# main.net
KiCad netlist of a schematic drawn in EAGLE
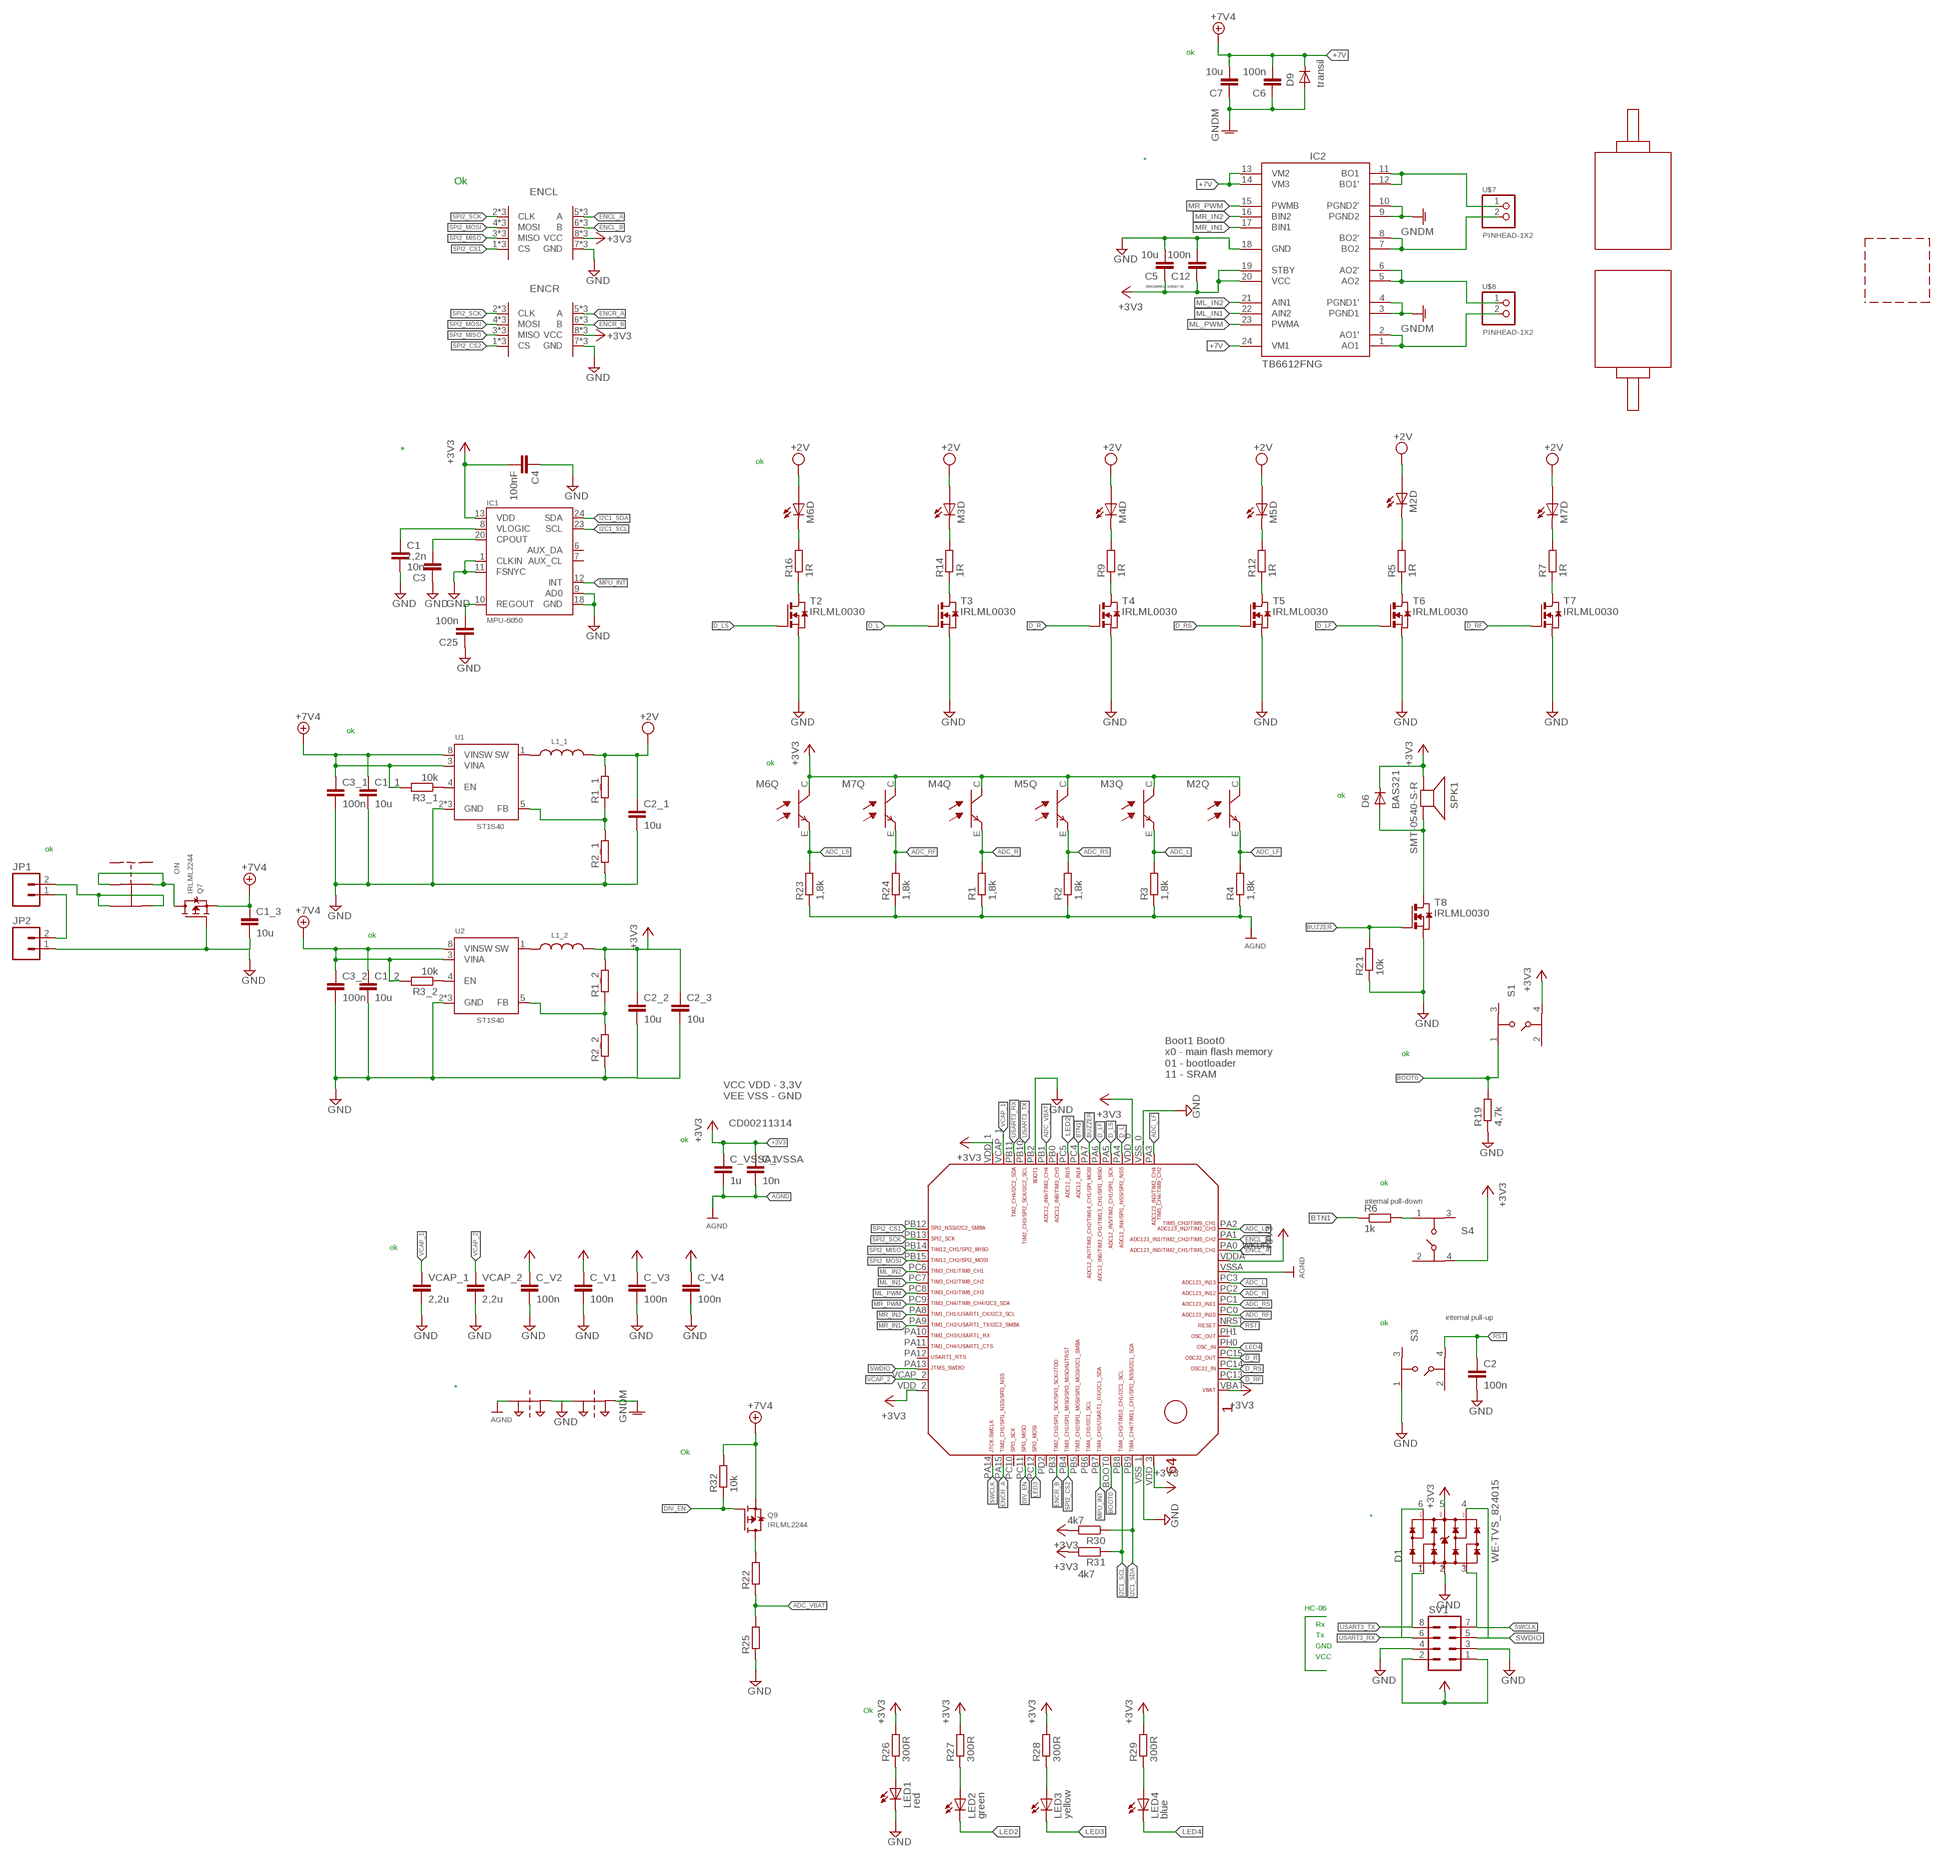
[diagram p0: schematic, sheet 1]

(export (version "E")
  (design (tool "Eeschema 10.0.6"))
  (components
    (comp (ref "C1")
      (value "10n")
      (footprint "eagle-import:C0603")
      (libsource (lib "eagle-import") (part "C-EUC0603"))
    )
    (comp (ref "C1_1")
      (value "10u")
      (footprint "eagle-import:C0805")
      (libsource (lib "eagle-import") (part "C-EUC0805"))
    )
    (comp (ref "C1_2")
      (value "10u")
      (footprint "eagle-import:C0805")
      (libsource (lib "eagle-import") (part "C-EUC0805"))
    )
    (comp (ref "C1_3")
      (value "10u")
      (footprint "eagle-import:C0805")
      (libsource (lib "eagle-import") (part "C-EUC0805"))
    )
    (comp (ref "C2")
      (value "100n")
      (footprint "eagle-import:C0603")
      (libsource (lib "eagle-import") (part "C-EUC0603"))
    )
    (comp (ref "C2_1")
      (value "10u")
      (footprint "eagle-import:C0805")
      (libsource (lib "eagle-import") (part "C-EUC0805"))
    )
    (comp (ref "C2_2")
      (value "10u")
      (footprint "eagle-import:C0805")
      (libsource (lib "eagle-import") (part "C-EUC0805"))
    )
    (comp (ref "C2_3")
      (value "10u")
      (footprint "eagle-import:C0805")
      (libsource (lib "eagle-import") (part "C-EUC0805"))
    )
    (comp (ref "C3")
      (value "2,2n")
      (footprint "eagle-import:C0603")
      (libsource (lib "eagle-import") (part "C-EUC0603"))
    )
    (comp (ref "C3_1")
      (value "100n")
      (footprint "eagle-import:C0603")
      (libsource (lib "eagle-import") (part "C-EUC0603"))
    )
    (comp (ref "C3_2")
      (value "100n")
      (footprint "eagle-import:C0603")
      (libsource (lib "eagle-import") (part "C-EUC0603"))
    )
    (comp (ref "C4")
      (value "100nF")
      (footprint "eagle-import:C0603")
      (libsource (lib "eagle-import") (part "C-EUC0603"))
    )
    (comp (ref "C5")
      (value "10u")
      (footprint "eagle-import:C0805")
      (libsource (lib "eagle-import") (part "C-EUC0805"))
    )
    (comp (ref "C6")
      (value "100n")
      (footprint "eagle-import:C0603")
      (libsource (lib "eagle-import") (part "C-EUC0603"))
    )
    (comp (ref "C7")
      (value "10u")
      (footprint "eagle-import:C1206")
      (libsource (lib "eagle-import") (part "C-EUC1206"))
    )
    (comp (ref "C12")
      (value "100n")
      (footprint "eagle-import:C0603")
      (libsource (lib "eagle-import") (part "C-EUC0603"))
    )
    (comp (ref "C25")
      (value "100n")
      (footprint "eagle-import:C0603")
      (libsource (lib "eagle-import") (part "C-EUC0603"))
    )
    (comp (ref "C_V1")
      (value "100n")
      (footprint "eagle-import:C0603")
      (libsource (lib "eagle-import") (part "C-EUC0603"))
    )
    (comp (ref "C_V2")
      (value "100n")
      (footprint "eagle-import:C0603")
      (libsource (lib "eagle-import") (part "C-EUC0603"))
    )
    (comp (ref "C_V3")
      (value "100n")
      (footprint "eagle-import:C0603")
      (libsource (lib "eagle-import") (part "C-EUC0603"))
    )
    (comp (ref "C_V4")
      (value "100n")
      (footprint "eagle-import:C0603")
      (libsource (lib "eagle-import") (part "C-EUC0603"))
    )
    (comp (ref "C_VSSA")
      (value "10n")
      (footprint "eagle-import:C0603")
      (libsource (lib "eagle-import") (part "C-EUC0603"))
    )
    (comp (ref "C_VSSA1")
      (value "1u")
      (footprint "eagle-import:C0603")
      (libsource (lib "eagle-import") (part "C-EUC0603"))
    )
    (comp (ref "D1")
      (value "WE-TVS_824015")
      (footprint "eagle-import:WE-TVS_SOT23-6L")
      (libsource (lib "eagle-import") (part "WE-TVS_824015"))
    )
    (comp (ref "D6")
      (value "BAS321")
      (footprint "eagle-import:SOD323(F)")
      (libsource (lib "eagle-import") (part "BAS321"))
    )
    (comp (ref "D9")
      (value "transil")
      (footprint "eagle-import:SOD323(F)")
      (libsource (lib "eagle-import") (part "BAS321"))
    )
    (comp (ref "IC1")
      (value "MPU-6050")
      (footprint "eagle-import:QFN.24.4X4")
      (libsource (lib "eagle-import") (part "MPU-6050"))
    )
    (comp (ref "IC2")
      (value "TB6612FNG")
      (footprint "eagle-import:SSOP24")
      (libsource (lib "eagle-import") (part "TB6612FNG"))
    )
    (comp (ref "JP1")
      (value "M02POLAR")
      (footprint "eagle-import:MOLEX-1X2")
      (libsource (lib "eagle-import") (part "M02POLAR"))
    )
    (comp (ref "JP2")
      (value "M02POLAR")
      (footprint "eagle-import:MOLEX-1X2")
      (libsource (lib "eagle-import") (part "M02POLAR"))
    )
    (comp (ref "L1")
      (value "LABITYNT")
      (footprint "eagle-import:LABIRYNT")
      (libsource (lib "eagle-import") (part "LABITYNT"))
    )
    (comp (ref "L1_1")
      (value "WE-MAIA_3015_78438335068")
      (footprint "eagle-import:WE-MAIA_3015")
      (libsource (lib "eagle-import") (part "WE-MAIA_3015_78438335068"))
    )
    (comp (ref "L1_2")
      (value "WE-MAIA_3015_78438335033")
      (footprint "eagle-import:WE-MAIA_3015")
      (libsource (lib "eagle-import") (part "WE-MAIA_3015_78438335033"))
    )
    (comp (ref "LED1")
      (value "red")
      (footprint "eagle-import:SML1206")
      (libsource (lib "eagle-import") (part "LEDSML1206"))
    )
    (comp (ref "LED2")
      (value "green")
      (footprint "eagle-import:SML1206")
      (libsource (lib "eagle-import") (part "LEDSML1206"))
    )
    (comp (ref "LED3")
      (value "yellow")
      (footprint "eagle-import:SML1206")
      (libsource (lib "eagle-import") (part "LEDSML1206"))
    )
    (comp (ref "LED4")
      (value "blue")
      (footprint "eagle-import:SML1206")
      (libsource (lib "eagle-import") (part "LEDSML1206"))
    )
    (comp (ref "M1")
      (value "MOTOR_MOUNT_V2")
      (footprint "eagle-import:MOTOR_MOUNT_V2")
      (libsource (lib "eagle-import") (part "MOTOR_MOUNT_V2"))
    )
    (comp (ref "M2")
      (value "LED_MOUNT")
      (footprint "eagle-import:LED_MOUNT")
      (libsource (lib "eagle-import") (part "LED_MOUNT"))
    )
    (comp (ref "M3")
      (value "LED_MOUNT")
      (footprint "eagle-import:LED_MOUNT")
      (libsource (lib "eagle-import") (part "LED_MOUNT"))
    )
    (comp (ref "M4")
      (value "LED_MOUNT")
      (footprint "eagle-import:LED_MOUNT")
      (libsource (lib "eagle-import") (part "LED_MOUNT"))
    )
    (comp (ref "M5")
      (value "LED_MOUNT")
      (footprint "eagle-import:LED_MOUNT")
      (libsource (lib "eagle-import") (part "LED_MOUNT"))
    )
    (comp (ref "M6")
      (value "LED_MOUNT")
      (footprint "eagle-import:LED_MOUNT")
      (libsource (lib "eagle-import") (part "LED_MOUNT"))
    )
    (comp (ref "M7")
      (value "LED_MOUNT")
      (footprint "eagle-import:LED_MOUNT")
      (libsource (lib "eagle-import") (part "LED_MOUNT"))
    )
    (comp (ref "ON")
      (value "PRZELACZNIK_SUWAKOWY")
      (footprint "eagle-import:PRZELACZNIK_SUWAKOWY")
      (libsource (lib "eagle-import") (part "PRZELACZNIK_SUWAKOWY"))
    )
    (comp (ref "PT1")
      (value "2PT_GND_TIE")
      (footprint "eagle-import:2PT_GND_TIE")
      (libsource (lib "eagle-import") (part "2PT_GND_TIE"))
    )
    (comp (ref "PT2")
      (value "2PT_GND_TIE")
      (footprint "eagle-import:2PT_GND_TIE")
      (libsource (lib "eagle-import") (part "2PT_GND_TIE"))
    )
    (comp (ref "Q7")
      (value "IRLML2244")
      (footprint "eagle-import:SOT23-R")
      (libsource (lib "eagle-import") (part "MOSFET-P"))
    )
    (comp (ref "Q9")
      (value "IRLML2244")
      (footprint "eagle-import:SOT23-R")
      (libsource (lib "eagle-import") (part "MOSFET-P"))
    )
    (comp (ref "R1")
      (value "1,8k")
      (footprint "eagle-import:R0603")
      (libsource (lib "eagle-import") (part "R-EU_R0603"))
    )
    (comp (ref "R1_1")
      (value "R-EU_R0603")
      (footprint "eagle-import:R0603")
      (libsource (lib "eagle-import") (part "R-EU_R0603"))
    )
    (comp (ref "R1_2")
      (value "R-EU_R0603")
      (footprint "eagle-import:R0603")
      (libsource (lib "eagle-import") (part "R-EU_R0603"))
    )
    (comp (ref "R2")
      (value "1,8k")
      (footprint "eagle-import:R0603")
      (libsource (lib "eagle-import") (part "R-EU_R0603"))
    )
    (comp (ref "R2_1")
      (value "R-EU_R0603")
      (footprint "eagle-import:R0603")
      (libsource (lib "eagle-import") (part "R-EU_R0603"))
    )
    (comp (ref "R2_2")
      (value "R-EU_R0603")
      (footprint "eagle-import:R0603")
      (libsource (lib "eagle-import") (part "R-EU_R0603"))
    )
    (comp (ref "R3")
      (value "1,8k")
      (footprint "eagle-import:R0603")
      (libsource (lib "eagle-import") (part "R-EU_R0603"))
    )
    (comp (ref "R3_1")
      (value "10k")
      (footprint "eagle-import:R0603")
      (libsource (lib "eagle-import") (part "R-EU_R0603"))
    )
    (comp (ref "R3_2")
      (value "10k")
      (footprint "eagle-import:R0603")
      (libsource (lib "eagle-import") (part "R-EU_R0603"))
    )
    (comp (ref "R4")
      (value "1,8k")
      (footprint "eagle-import:R0603")
      (libsource (lib "eagle-import") (part "R-EU_R0603"))
    )
    (comp (ref "R5")
      (value "1R")
      (footprint "eagle-import:R0603")
      (libsource (lib "eagle-import") (part "R-EU_R0603"))
    )
    (comp (ref "R6")
      (value "1k")
      (footprint "eagle-import:R0603")
      (libsource (lib "eagle-import") (part "R-EU_R0603"))
    )
    (comp (ref "R7")
      (value "1R")
      (footprint "eagle-import:R0603")
      (libsource (lib "eagle-import") (part "R-EU_R0603"))
    )
    (comp (ref "R9")
      (value "1R")
      (footprint "eagle-import:R0603")
      (libsource (lib "eagle-import") (part "R-EU_R0603"))
    )
    (comp (ref "R12")
      (value "1R")
      (footprint "eagle-import:R0603")
      (libsource (lib "eagle-import") (part "R-EU_R0603"))
    )
    (comp (ref "R14")
      (value "1R")
      (footprint "eagle-import:R0603")
      (libsource (lib "eagle-import") (part "R-EU_R0603"))
    )
    (comp (ref "R16")
      (value "1R")
      (footprint "eagle-import:R0603")
      (libsource (lib "eagle-import") (part "R-EU_R0603"))
    )
    (comp (ref "R19")
      (value "4,7k")
      (footprint "eagle-import:R0603")
      (libsource (lib "eagle-import") (part "R-EU_R0603"))
    )
    (comp (ref "R21")
      (value "10k")
      (footprint "eagle-import:R0603")
      (libsource (lib "eagle-import") (part "R-EU_R0603"))
    )
    (comp (ref "R22")
      (value "R-EU_R0603")
      (footprint "eagle-import:R0603")
      (libsource (lib "eagle-import") (part "resistor_R-EU_R0603"))
    )
    (comp (ref "R23")
      (value "1,8k")
      (footprint "eagle-import:R0603")
      (libsource (lib "eagle-import") (part "R-EU_R0603"))
    )
    (comp (ref "R24")
      (value "1,8k")
      (footprint "eagle-import:R0603")
      (libsource (lib "eagle-import") (part "R-EU_R0603"))
    )
    (comp (ref "R25")
      (value "R-EU_R0603")
      (footprint "eagle-import:R0603")
      (libsource (lib "eagle-import") (part "resistor_R-EU_R0603"))
    )
    (comp (ref "R26")
      (value "300R")
      (footprint "eagle-import:R0603")
      (libsource (lib "eagle-import") (part "resistor_R-EU_R0603"))
    )
    (comp (ref "R27")
      (value "300R")
      (footprint "eagle-import:R0603")
      (libsource (lib "eagle-import") (part "resistor_R-EU_R0603"))
    )
    (comp (ref "R28")
      (value "300R")
      (footprint "eagle-import:R0603")
      (libsource (lib "eagle-import") (part "resistor_R-EU_R0603"))
    )
    (comp (ref "R29")
      (value "300R")
      (footprint "eagle-import:R0603")
      (libsource (lib "eagle-import") (part "resistor_R-EU_R0603"))
    )
    (comp (ref "R30")
      (value "4k7")
      (footprint "eagle-import:R0603")
      (libsource (lib "eagle-import") (part "R-EU_R0603"))
    )
    (comp (ref "R31")
      (value "4k7")
      (footprint "eagle-import:R0603")
      (libsource (lib "eagle-import") (part "R-EU_R0603"))
    )
    (comp (ref "R32")
      (value "10k")
      (footprint "eagle-import:R0603")
      (libsource (lib "eagle-import") (part "resistor_R-EU_R0603"))
    )
    (comp (ref "S1")
      (value "434153017835")
      (footprint "eagle-import:434153017835")
      (libsource (lib "eagle-import") (part "434153017835"))
    )
    (comp (ref "S3")
      (value "434153017835")
      (footprint "eagle-import:434153017835")
      (libsource (lib "eagle-import") (part "434153017835"))
    )
    (comp (ref "S4")
      (value "434153017835")
      (footprint "eagle-import:434153017835")
      (libsource (lib "eagle-import") (part "434153017835"))
    )
    (comp (ref "SPK1")
      (value "SMT-0540-S-R")
      (footprint "eagle-import:SMT-0540-S-R")
      (libsource (lib "eagle-import") (part "SMT-0540-S-R"))
    )
    (comp (ref "SV1")
      (value "MA04-2")
      (footprint "eagle-import:MA04-2")
      (libsource (lib "eagle-import") (part "MA04-2"))
    )
    (comp (ref "T2")
      (value "IRLML0030")
      (footprint "eagle-import:SOT-23")
      (libsource (lib "eagle-import") (part "NMOSSOT23"))
    )
    (comp (ref "T3")
      (value "IRLML0030")
      (footprint "eagle-import:SOT-23")
      (libsource (lib "eagle-import") (part "NMOSSOT23"))
    )
    (comp (ref "T4")
      (value "IRLML0030")
      (footprint "eagle-import:SOT-23")
      (libsource (lib "eagle-import") (part "NMOSSOT23"))
    )
    (comp (ref "T5")
      (value "IRLML0030")
      (footprint "eagle-import:SOT-23")
      (libsource (lib "eagle-import") (part "NMOSSOT23"))
    )
    (comp (ref "T6")
      (value "IRLML0030")
      (footprint "eagle-import:SOT-23")
      (libsource (lib "eagle-import") (part "NMOSSOT23"))
    )
    (comp (ref "T7")
      (value "IRLML0030")
      (footprint "eagle-import:SOT-23")
      (libsource (lib "eagle-import") (part "NMOSSOT23"))
    )
    (comp (ref "T8")
      (value "IRLML0030")
      (footprint "eagle-import:SOT-23")
      (libsource (lib "eagle-import") (part "NMOSSOT23"))
    )
    (comp (ref "U$7")
      (value "PINHEAD-1X2")
      (footprint "eagle-import:PIHEAD-1X2")
      (libsource (lib "eagle-import") (part "PINHEAD-1X2"))
    )
    (comp (ref "U$8")
      (value "PINHEAD-1X2")
      (footprint "eagle-import:PIHEAD-1X2")
      (libsource (lib "eagle-import") (part "PINHEAD-1X2"))
    )
    (comp (ref "U$9")
      (value "ENCODER_MOUNT")
      (footprint "eagle-import:ENCODER_MOUNT")
      (libsource (lib "eagle-import") (part "ENCODER_MOUNT"))
    )
    (comp (ref "U$10")
      (value "ENCODER_MOUNT")
      (footprint "eagle-import:ENCODER_MOUNT")
      (libsource (lib "eagle-import") (part "ENCODER_MOUNT"))
    )
    (comp (ref "U1")
      (value "ST1S40")
      (footprint "eagle-import:SO8")
      (libsource (lib "eagle-import") (part "ST1S40"))
    )
    (comp (ref "U2")
      (value "ST1S40")
      (footprint "eagle-import:SO8")
      (libsource (lib "eagle-import") (part "ST1S40"))
    )
    (comp (ref "U3")
      (value "STM32F4X5")
      (footprint "eagle-import:STM32F4-LQFP64")
      (libsource (lib "eagle-import") (part "STM32F4X5"))
    )
    (comp (ref "VCAP_1")
      (value "2,2u")
      (footprint "eagle-import:C0603")
      (libsource (lib "eagle-import") (part "C-EUC0603"))
    )
    (comp (ref "VCAP_2")
      (value "2,2u")
      (footprint "eagle-import:C0603")
      (libsource (lib "eagle-import") (part "C-EUC0603"))
    )
  )
  (nets
    (net (code "1") (name "+2V") (class "Default")
      (node (ref "C2_1") (pin "1") (pinfunction "1_1") (pintype "passive"))
      (node (ref "L1_1") (pin "2") (pinfunction "2_2") (pintype "passive"))
      (node (ref "M2") (pin "+") (pinfunction "A_+") (pintype "passive"))
      (node (ref "M3") (pin "+") (pinfunction "A_+") (pintype "passive"))
      (node (ref "M4") (pin "+") (pinfunction "A_+") (pintype "passive"))
      (node (ref "M5") (pin "+") (pinfunction "A_+") (pintype "passive"))
      (node (ref "M6") (pin "+") (pinfunction "A_+") (pintype "passive"))
      (node (ref "M7") (pin "+") (pinfunction "A_+") (pintype "passive"))
      (node (ref "R1_1") (pin "2") (pinfunction "2_2") (pintype "passive"))
    )
    (net (code "2") (name "+3V3") (class "Default")
      (node (ref "C12") (pin "1") (pinfunction "1_1") (pintype "passive"))
      (node (ref "C2_2") (pin "1") (pinfunction "1_1") (pintype "passive"))
      (node (ref "C2_3") (pin "1") (pinfunction "1_1") (pintype "passive"))
      (node (ref "C4") (pin "2") (pinfunction "2_2") (pintype "passive"))
      (node (ref "C5") (pin "1") (pinfunction "1_1") (pintype "passive"))
      (node (ref "C_V1") (pin "1") (pinfunction "1_1") (pintype "passive"))
      (node (ref "C_V2") (pin "1") (pinfunction "1_1") (pintype "passive"))
      (node (ref "C_V3") (pin "1") (pinfunction "1_1") (pintype "passive"))
      (node (ref "C_V4") (pin "1") (pinfunction "1_1") (pintype "passive"))
      (node (ref "C_VSSA") (pin "1") (pinfunction "1_1") (pintype "passive"))
      (node (ref "C_VSSA1") (pin "1") (pinfunction "1_1") (pintype "passive"))
      (node (ref "D1") (pin "5") (pinfunction "VDD_5") (pintype "power_in"))
      (node (ref "D6") (pin "1") (pinfunction "K_1") (pintype "passive"))
      (node (ref "IC1") (pin "13") (pinfunction "VDD_13") (pintype "bidirectional"))
      (node (ref "IC2") (pin "19") (pinfunction "STBY_19") (pintype "input"))
      (node (ref "IC2") (pin "20") (pinfunction "VCC_20") (pintype "power_in"))
      (node (ref "L1_2") (pin "2") (pinfunction "2_2") (pintype "passive"))
      (node (ref "M2") (pin "C") (pinfunction "C_C") (pintype "bidirectional"))
      (node (ref "M3") (pin "C") (pinfunction "C_C") (pintype "bidirectional"))
      (node (ref "M4") (pin "C") (pinfunction "C_C") (pintype "bidirectional"))
      (node (ref "M5") (pin "C") (pinfunction "C_C") (pintype "bidirectional"))
      (node (ref "M6") (pin "C") (pinfunction "C_C") (pintype "bidirectional"))
      (node (ref "M7") (pin "C") (pinfunction "C_C") (pintype "bidirectional"))
      (node (ref "R1_2") (pin "2") (pinfunction "2_2") (pintype "passive"))
      (node (ref "R26") (pin "2") (pinfunction "2_2") (pintype "passive"))
      (node (ref "R27") (pin "2") (pinfunction "2_2") (pintype "passive"))
      (node (ref "R28") (pin "2") (pinfunction "2_2") (pintype "passive"))
      (node (ref "R29") (pin "2") (pinfunction "2_2") (pintype "passive"))
      (node (ref "R30") (pin "2") (pinfunction "2_2") (pintype "passive"))
      (node (ref "R31") (pin "2") (pinfunction "2_2") (pintype "passive"))
      (node (ref "S1") (pin "4") (pinfunction "4_4") (pintype "passive"))
      (node (ref "S4") (pin "4") (pinfunction "4_4") (pintype "passive"))
      (node (ref "SPK1") (pin "-") (pinfunction "+_-") (pintype "passive"))
      (node (ref "SV1") (pin "1") (pinfunction "1_1") (pintype "passive"))
      (node (ref "SV1") (pin "2") (pinfunction "2_2") (pintype "passive"))
      (node (ref "U$10") (pin "8") (pinfunction "VCC_8") (pintype "bidirectional"))
      (node (ref "U$10") (pin "8_1") (pinfunction "VCC_8_1") (pintype "bidirectional"))
      (node (ref "U$10") (pin "8_2") (pinfunction "VCC_8_2") (pintype "bidirectional"))
      (node (ref "U$9") (pin "8") (pinfunction "VCC_8") (pintype "bidirectional"))
      (node (ref "U$9") (pin "8_1") (pinfunction "VCC_8_1") (pintype "bidirectional"))
      (node (ref "U$9") (pin "8_2") (pinfunction "VCC_8_2") (pintype "bidirectional"))
      (node (ref "U3") (pin "VBAT") (pinfunction "VBAT_VBAT") (pintype "bidirectional"))
      (node (ref "U3") (pin "VDDA") (pinfunction "VDDA_VDDA") (pintype "bidirectional"))
      (node (ref "U3") (pin "VDD_0") (pinfunction "VDD_0_VDD_0") (pintype "bidirectional"))
      (node (ref "U3") (pin "VDD_1") (pinfunction "VDD_1_VDD_1") (pintype "bidirectional"))
      (node (ref "U3") (pin "VDD_2") (pinfunction "VDD_2_VDD_2") (pintype "bidirectional"))
      (node (ref "U3") (pin "VDD_3") (pinfunction "VDD_3_VDD_3") (pintype "bidirectional"))
    )
    (net (code "3") (name "+7V") (class "Default")
      (node (ref "C1_1") (pin "1") (pinfunction "1_1") (pintype "passive"))
      (node (ref "C1_2") (pin "1") (pinfunction "1_1") (pintype "passive"))
      (node (ref "C1_3") (pin "1") (pinfunction "1_1") (pintype "passive"))
      (node (ref "C3_1") (pin "1") (pinfunction "1_1") (pintype "passive"))
      (node (ref "C3_2") (pin "1") (pinfunction "1_1") (pintype "passive"))
      (node (ref "C6") (pin "2") (pinfunction "2_2") (pintype "passive"))
      (node (ref "C7") (pin "2") (pinfunction "2_2") (pintype "passive"))
      (node (ref "D9") (pin "1") (pinfunction "K_1") (pintype "passive"))
      (node (ref "IC2") (pin "13") (pinfunction "VM2_13") (pintype "power_in"))
      (node (ref "IC2") (pin "14") (pinfunction "VM3_14") (pintype "power_in"))
      (node (ref "IC2") (pin "24") (pinfunction "VM1_24") (pintype "power_in"))
      (node (ref "Q7") (pin "2") (pinfunction "S_2") (pintype "passive"))
      (node (ref "Q9") (pin "2") (pinfunction "S_2") (pintype "passive"))
      (node (ref "R32") (pin "2") (pinfunction "2_2") (pintype "passive"))
      (node (ref "R3_1") (pin "2") (pinfunction "2_2") (pintype "passive"))
      (node (ref "R3_2") (pin "2") (pinfunction "2_2") (pintype "passive"))
      (node (ref "U1") (pin "3") (pinfunction "VINA_3") (pintype "bidirectional"))
      (node (ref "U1") (pin "8") (pinfunction "VINSW_8") (pintype "bidirectional"))
      (node (ref "U2") (pin "3") (pinfunction "VINA_3") (pintype "bidirectional"))
      (node (ref "U2") (pin "8") (pinfunction "VINSW_8") (pintype "bidirectional"))
    )
    (net (code "4") (name "ADC_L") (class "Default")
      (node (ref "M3") (pin "E") (pinfunction "E_E") (pintype "bidirectional"))
      (node (ref "R3") (pin "2") (pinfunction "2_2") (pintype "passive"))
      (node (ref "U3") (pin "PC3") (pinfunction "PC3_PC3") (pintype "bidirectional"))
    )
    (net (code "5") (name "ADC_LF") (class "Default")
      (node (ref "M2") (pin "E") (pinfunction "E_E") (pintype "bidirectional"))
      (node (ref "R4") (pin "2") (pinfunction "2_2") (pintype "passive"))
      (node (ref "U3") (pin "PA3") (pinfunction "PA3_PA3") (pintype "bidirectional"))
    )
    (net (code "6") (name "ADC_LS") (class "Default")
      (node (ref "M6") (pin "E") (pinfunction "E_E") (pintype "bidirectional"))
      (node (ref "R23") (pin "2") (pinfunction "2_2") (pintype "passive"))
      (node (ref "U3") (pin "PA2") (pinfunction "PA2_PA2") (pintype "bidirectional"))
    )
    (net (code "7") (name "ADC_R") (class "Default")
      (node (ref "M4") (pin "E") (pinfunction "E_E") (pintype "bidirectional"))
      (node (ref "R1") (pin "2") (pinfunction "2_2") (pintype "passive"))
      (node (ref "U3") (pin "PC2") (pinfunction "PC2_PC2") (pintype "bidirectional"))
    )
    (net (code "8") (name "ADC_RF") (class "Default")
      (node (ref "M7") (pin "E") (pinfunction "E_E") (pintype "bidirectional"))
      (node (ref "R24") (pin "2") (pinfunction "2_2") (pintype "passive"))
      (node (ref "U3") (pin "PC0") (pinfunction "PC0_PC0") (pintype "bidirectional"))
    )
    (net (code "9") (name "ADC_RS") (class "Default")
      (node (ref "M5") (pin "E") (pinfunction "E_E") (pintype "bidirectional"))
      (node (ref "R2") (pin "2") (pinfunction "2_2") (pintype "passive"))
      (node (ref "U3") (pin "PC1") (pinfunction "PC1_PC1") (pintype "bidirectional"))
    )
    (net (code "10") (name "ADC_VBAT") (class "Default")
      (node (ref "R22") (pin "1") (pinfunction "1_1") (pintype "passive"))
      (node (ref "R25") (pin "2") (pinfunction "2_2") (pintype "passive"))
      (node (ref "U3") (pin "PB1") (pinfunction "PB1_PB1") (pintype "bidirectional"))
    )
    (net (code "11") (name "AGND") (class "Default")
      (node (ref "C_VSSA") (pin "2") (pinfunction "2_2") (pintype "passive"))
      (node (ref "C_VSSA1") (pin "2") (pinfunction "2_2") (pintype "passive"))
      (node (ref "PT1") (pin "P$1") (pinfunction "P$1_P$1") (pintype "bidirectional"))
      (node (ref "R1") (pin "1") (pinfunction "1_1") (pintype "passive"))
      (node (ref "R2") (pin "1") (pinfunction "1_1") (pintype "passive"))
      (node (ref "R23") (pin "1") (pinfunction "1_1") (pintype "passive"))
      (node (ref "R24") (pin "1") (pinfunction "1_1") (pintype "passive"))
      (node (ref "R3") (pin "1") (pinfunction "1_1") (pintype "passive"))
      (node (ref "R4") (pin "1") (pinfunction "1_1") (pintype "passive"))
      (node (ref "U3") (pin "VSSA") (pinfunction "VSSA_VSSA") (pintype "bidirectional"))
    )
    (net (code "12") (name "BOOT0") (class "Default")
      (node (ref "R19") (pin "2") (pinfunction "2_2") (pintype "passive"))
      (node (ref "S1") (pin "1") (pinfunction "1_1") (pintype "passive"))
      (node (ref "U3") (pin "BOOT0") (pinfunction "BOOT0_BOOT0") (pintype "bidirectional"))
    )
    (net (code "13") (name "BTN1") (class "Default")
      (node (ref "R6") (pin "1") (pinfunction "1_1") (pintype "passive"))
      (node (ref "U3") (pin "PC4") (pinfunction "PC4_PC4") (pintype "bidirectional"))
    )
    (net (code "14") (name "BUZZER") (class "Default")
      (node (ref "R21") (pin "2") (pinfunction "2_2") (pintype "passive"))
      (node (ref "T8") (pin "3") (pinfunction "G_3") (pintype "passive"))
      (node (ref "U3") (pin "PA7") (pinfunction "PA7_PA7") (pintype "bidirectional"))
    )
    (net (code "15") (name "DIV_EN") (class "Default")
      (node (ref "Q9") (pin "1") (pinfunction "G_1") (pintype "passive"))
      (node (ref "R32") (pin "1") (pinfunction "1_1") (pintype "passive"))
      (node (ref "U3") (pin "PC11") (pinfunction "PC11_PC11") (pintype "bidirectional"))
    )
    (net (code "16") (name "D_L") (class "Default")
      (node (ref "T3") (pin "3") (pinfunction "G_3") (pintype "passive"))
      (node (ref "U3") (pin "PA4") (pinfunction "PA4_PA4") (pintype "bidirectional"))
    )
    (net (code "17") (name "D_LF") (class "Default")
      (node (ref "T6") (pin "3") (pinfunction "G_3") (pintype "passive"))
      (node (ref "U3") (pin "PA6") (pinfunction "PA6_PA6") (pintype "bidirectional"))
    )
    (net (code "18") (name "D_LS") (class "Default")
      (node (ref "T2") (pin "3") (pinfunction "G_3") (pintype "passive"))
      (node (ref "U3") (pin "PA5") (pinfunction "PA5_PA5") (pintype "bidirectional"))
    )
    (net (code "19") (name "D_R") (class "Default")
      (node (ref "T4") (pin "3") (pinfunction "G_3") (pintype "passive"))
      (node (ref "U3") (pin "PC15") (pinfunction "PC15_PC15") (pintype "bidirectional"))
    )
    (net (code "20") (name "D_RF") (class "Default")
      (node (ref "T7") (pin "3") (pinfunction "G_3") (pintype "passive"))
      (node (ref "U3") (pin "PC13") (pinfunction "PC13_PC13") (pintype "bidirectional"))
    )
    (net (code "21") (name "D_RS") (class "Default")
      (node (ref "T5") (pin "3") (pinfunction "G_3") (pintype "passive"))
      (node (ref "U3") (pin "PC14") (pinfunction "PC14_PC14") (pintype "bidirectional"))
    )
    (net (code "22") (name "ENCL_A") (class "Default")
      (node (ref "U$9") (pin "5") (pinfunction "A_5") (pintype "bidirectional"))
      (node (ref "U$9") (pin "5_1") (pinfunction "A_5_1") (pintype "bidirectional"))
      (node (ref "U$9") (pin "5_2") (pinfunction "A_5_2") (pintype "bidirectional"))
      (node (ref "U3") (pin "PA0_WKUP") (pinfunction "PA0_AKUP_PA0_WKUP") (pintype "bidirectional"))
    )
    (net (code "23") (name "ENCL_B") (class "Default")
      (node (ref "U$9") (pin "6") (pinfunction "B_6") (pintype "bidirectional"))
      (node (ref "U$9") (pin "6_1") (pinfunction "B_6_1") (pintype "bidirectional"))
      (node (ref "U$9") (pin "6_2") (pinfunction "B_6_2") (pintype "bidirectional"))
      (node (ref "U3") (pin "PA1") (pinfunction "PA1_PA1") (pintype "bidirectional"))
    )
    (net (code "24") (name "ENCR_A") (class "Default")
      (node (ref "U$10") (pin "5") (pinfunction "A_5") (pintype "bidirectional"))
      (node (ref "U$10") (pin "5_1") (pinfunction "A_5_1") (pintype "bidirectional"))
      (node (ref "U$10") (pin "5_2") (pinfunction "A_5_2") (pintype "bidirectional"))
      (node (ref "U3") (pin "PA15") (pinfunction "PA15_PA15") (pintype "bidirectional"))
    )
    (net (code "25") (name "ENCR_B") (class "Default")
      (node (ref "U$10") (pin "6") (pinfunction "B_6") (pintype "bidirectional"))
      (node (ref "U$10") (pin "6_1") (pinfunction "B_6_1") (pintype "bidirectional"))
      (node (ref "U$10") (pin "6_2") (pinfunction "B_6_2") (pintype "bidirectional"))
      (node (ref "U3") (pin "PB3") (pinfunction "PB3_PB3") (pintype "bidirectional"))
    )
    (net (code "26") (name "GND") (class "Default")
      (node (ref "C1") (pin "2") (pinfunction "2_2") (pintype "passive"))
      (node (ref "C12") (pin "2") (pinfunction "2_2") (pintype "passive"))
      (node (ref "C1_1") (pin "2") (pinfunction "2_2") (pintype "passive"))
      (node (ref "C1_2") (pin "2") (pinfunction "2_2") (pintype "passive"))
      (node (ref "C1_3") (pin "2") (pinfunction "2_2") (pintype "passive"))
      (node (ref "C2") (pin "2") (pinfunction "2_2") (pintype "passive"))
      (node (ref "C25") (pin "1") (pinfunction "1_1") (pintype "passive"))
      (node (ref "C2_1") (pin "2") (pinfunction "2_2") (pintype "passive"))
      (node (ref "C2_2") (pin "2") (pinfunction "2_2") (pintype "passive"))
      (node (ref "C2_3") (pin "2") (pinfunction "2_2") (pintype "passive"))
      (node (ref "C3") (pin "1") (pinfunction "1_1") (pintype "passive"))
      (node (ref "C3_1") (pin "2") (pinfunction "2_2") (pintype "passive"))
      (node (ref "C3_2") (pin "2") (pinfunction "2_2") (pintype "passive"))
      (node (ref "C4") (pin "1") (pinfunction "1_1") (pintype "passive"))
      (node (ref "C5") (pin "2") (pinfunction "2_2") (pintype "passive"))
      (node (ref "C_V1") (pin "2") (pinfunction "2_2") (pintype "passive"))
      (node (ref "C_V2") (pin "2") (pinfunction "2_2") (pintype "passive"))
      (node (ref "C_V3") (pin "2") (pinfunction "2_2") (pintype "passive"))
      (node (ref "C_V4") (pin "2") (pinfunction "2_2") (pintype "passive"))
      (node (ref "D1") (pin "2") (pinfunction "GND_2") (pintype "power_in"))
      (node (ref "IC1") (pin "1") (pinfunction "CLKIN_1") (pintype "bidirectional"))
      (node (ref "IC1") (pin "11") (pinfunction "FSNYC_11") (pintype "bidirectional"))
      (node (ref "IC1") (pin "18") (pinfunction "GND_18") (pintype "bidirectional"))
      (node (ref "IC1") (pin "9") (pinfunction "AD0_9") (pintype "bidirectional"))
      (node (ref "IC2") (pin "18") (pinfunction "GND_18") (pintype "power_in"))
      (node (ref "JP2") (pin "1") (pinfunction "1_1") (pintype "passive"))
      (node (ref "LED1") (pin "C") (pinfunction "C_C") (pintype "passive"))
      (node (ref "PT1") (pin "P$2") (pinfunction "P$2_P$2") (pintype "bidirectional"))
      (node (ref "PT2") (pin "P$1") (pinfunction "P$1_P$1") (pintype "bidirectional"))
      (node (ref "Q7") (pin "1") (pinfunction "G_1") (pintype "passive"))
      (node (ref "R19") (pin "1") (pinfunction "1_1") (pintype "passive"))
      (node (ref "R21") (pin "1") (pinfunction "1_1") (pintype "passive"))
      (node (ref "R25") (pin "1") (pinfunction "1_1") (pintype "passive"))
      (node (ref "R2_1") (pin "1") (pinfunction "1_1") (pintype "passive"))
      (node (ref "R2_2") (pin "1") (pinfunction "1_1") (pintype "passive"))
      (node (ref "S3") (pin "1") (pinfunction "1_1") (pintype "passive"))
      (node (ref "SV1") (pin "3") (pinfunction "3_3") (pintype "passive"))
      (node (ref "SV1") (pin "4") (pinfunction "4_4") (pintype "passive"))
      (node (ref "T2") (pin "2") (pinfunction "S_2") (pintype "passive"))
      (node (ref "T3") (pin "2") (pinfunction "S_2") (pintype "passive"))
      (node (ref "T4") (pin "2") (pinfunction "S_2") (pintype "passive"))
      (node (ref "T5") (pin "2") (pinfunction "S_2") (pintype "passive"))
      (node (ref "T6") (pin "2") (pinfunction "S_2") (pintype "passive"))
      (node (ref "T7") (pin "2") (pinfunction "S_2") (pintype "passive"))
      (node (ref "T8") (pin "2") (pinfunction "S_2") (pintype "passive"))
      (node (ref "U$10") (pin "7") (pinfunction "GND_7") (pintype "bidirectional"))
      (node (ref "U$10") (pin "7_1") (pinfunction "GND_7_1") (pintype "bidirectional"))
      (node (ref "U$10") (pin "7_2") (pinfunction "GND_7_2") (pintype "bidirectional"))
      (node (ref "U$9") (pin "7") (pinfunction "GND_7") (pintype "bidirectional"))
      (node (ref "U$9") (pin "7_1") (pinfunction "GND_7_1") (pintype "bidirectional"))
      (node (ref "U$9") (pin "7_2") (pinfunction "GND_7_2") (pintype "bidirectional"))
      (node (ref "U1") (pin "2") (pinfunction "GND_2") (pintype "bidirectional"))
      (node (ref "U1") (pin "6") (pinfunction "GND_6") (pintype "bidirectional"))
      (node (ref "U1") (pin "7") (pinfunction "GND_7") (pintype "bidirectional"))
      (node (ref "U2") (pin "2") (pinfunction "GND_2") (pintype "bidirectional"))
      (node (ref "U2") (pin "6") (pinfunction "GND_6") (pintype "bidirectional"))
      (node (ref "U2") (pin "7") (pinfunction "GND_7") (pintype "bidirectional"))
      (node (ref "U3") (pin "PB2") (pinfunction "PB2_PB2") (pintype "bidirectional"))
      (node (ref "U3") (pin "VSS_0") (pinfunction "VSS_0_VSS_0") (pintype "bidirectional"))
      (node (ref "U3") (pin "VSS_1") (pinfunction "VSS_1_VSS_1") (pintype "bidirectional"))
      (node (ref "VCAP_1") (pin "2") (pinfunction "2_2") (pintype "passive"))
      (node (ref "VCAP_2") (pin "2") (pinfunction "2_2") (pintype "passive"))
    )
    (net (code "27") (name "GNDM") (class "Default")
      (node (ref "C6") (pin "1") (pinfunction "1_1") (pintype "passive"))
      (node (ref "C7") (pin "1") (pinfunction "1_1") (pintype "passive"))
      (node (ref "D9") (pin "2") (pinfunction "A_2") (pintype "passive"))
      (node (ref "IC2") (pin "10") (pinfunction "PGND2'_10") (pintype "power_in"))
      (node (ref "IC2") (pin "3") (pinfunction "PGND1_3") (pintype "power_in"))
      (node (ref "IC2") (pin "4") (pinfunction "PGND1'_4") (pintype "power_in"))
      (node (ref "IC2") (pin "9") (pinfunction "PGND2_9") (pintype "power_in"))
      (node (ref "PT2") (pin "P$2") (pinfunction "P$2_P$2") (pintype "bidirectional"))
    )
    (net (code "28") (name "I2C1_SCL") (class "Default")
      (node (ref "IC1") (pin "23") (pinfunction "SCL_23") (pintype "bidirectional"))
      (node (ref "R31") (pin "1") (pinfunction "1_1") (pintype "passive"))
      (node (ref "U3") (pin "PB8") (pinfunction "PB8_PB8") (pintype "bidirectional"))
    )
    (net (code "29") (name "I2C1_SDA") (class "Default")
      (node (ref "IC1") (pin "24") (pinfunction "SDA_24") (pintype "bidirectional"))
      (node (ref "R30") (pin "1") (pinfunction "1_1") (pintype "passive"))
      (node (ref "U3") (pin "PB9") (pinfunction "PB9_PB9") (pintype "bidirectional"))
    )
    (net (code "30") (name "LED2") (class "Default")
      (node (ref "LED2") (pin "C") (pinfunction "C_C") (pintype "passive"))
      (node (ref "U3") (pin "PC5") (pinfunction "PC5_PC5") (pintype "bidirectional"))
    )
    (net (code "31") (name "LED3") (class "Default")
      (node (ref "LED3") (pin "C") (pinfunction "C_C") (pintype "passive"))
      (node (ref "U3") (pin "PC12") (pinfunction "PC12_PC12") (pintype "bidirectional"))
    )
    (net (code "32") (name "LED4") (class "Default")
      (node (ref "LED4") (pin "C") (pinfunction "C_C") (pintype "passive"))
      (node (ref "U3") (pin "PH0") (pinfunction "PH0_PH0") (pintype "bidirectional"))
    )
    (net (code "33") (name "ML_IN1") (class "Default")
      (node (ref "IC2") (pin "22") (pinfunction "AIN2_22") (pintype "input"))
      (node (ref "U3") (pin "PC7") (pinfunction "PC7_PC7") (pintype "bidirectional"))
    )
    (net (code "34") (name "ML_IN2") (class "Default")
      (node (ref "IC2") (pin "21") (pinfunction "AIN1_21") (pintype "input"))
      (node (ref "U3") (pin "PC6") (pinfunction "PC6_PC6") (pintype "bidirectional"))
    )
    (net (code "35") (name "ML_PWM") (class "Default")
      (node (ref "IC2") (pin "23") (pinfunction "PWMA_23") (pintype "input"))
      (node (ref "U3") (pin "PC8") (pinfunction "PC8_PC8") (pintype "bidirectional"))
    )
    (net (code "36") (name "MPU_INT") (class "Default")
      (node (ref "IC1") (pin "12") (pinfunction "INT_12") (pintype "bidirectional"))
      (node (ref "U3") (pin "PB7") (pinfunction "PB7_PB7") (pintype "bidirectional"))
    )
    (net (code "37") (name "MR_IN1") (class "Default")
      (node (ref "IC2") (pin "17") (pinfunction "BIN1_17") (pintype "input"))
      (node (ref "U3") (pin "PA9") (pinfunction "PA9_PA9") (pintype "bidirectional"))
    )
    (net (code "38") (name "MR_IN2") (class "Default")
      (node (ref "IC2") (pin "16") (pinfunction "BIN2_16") (pintype "input"))
      (node (ref "U3") (pin "PA8") (pinfunction "PA8_PA8") (pintype "bidirectional"))
    )
    (net (code "39") (name "MR_PWM") (class "Default")
      (node (ref "IC2") (pin "15") (pinfunction "PWMB_15") (pintype "input"))
      (node (ref "U3") (pin "PC9") (pinfunction "PC9_PC9") (pintype "bidirectional"))
    )
    (net (code "40") (name "Net-(D6-A)") (class "Default")
      (node (ref "D6") (pin "2") (pinfunction "A_2") (pintype "passive"))
      (node (ref "SPK1") (pin "+") (pinfunction "-_+") (pintype "passive"))
      (node (ref "T8") (pin "1") (pinfunction "D_1") (pintype "passive"))
    )
    (net (code "41") (name "Net-(IC1-CPOUT)") (class "Default")
      (node (ref "C3") (pin "2") (pinfunction "2_2") (pintype "passive"))
      (node (ref "IC1") (pin "20") (pinfunction "CPOUT_20") (pintype "bidirectional"))
    )
    (net (code "42") (name "Net-(IC1-REGOUT)") (class "Default")
      (node (ref "C25") (pin "2") (pinfunction "2_2") (pintype "passive"))
      (node (ref "IC1") (pin "10") (pinfunction "REGOUT_10") (pintype "bidirectional"))
    )
    (net (code "43") (name "Net-(IC1-VLOGIC)") (class "Default")
      (node (ref "C1") (pin "1") (pinfunction "1_1") (pintype "passive"))
      (node (ref "IC1") (pin "8") (pinfunction "VLOGIC_8") (pintype "bidirectional"))
    )
    (net (code "44") (name "Net-(IC2-AO1')") (class "Default")
      (node (ref "IC2") (pin "1") (pinfunction "AO1_1") (pintype "output"))
      (node (ref "IC2") (pin "2") (pinfunction "AO1'_2") (pintype "output"))
      (node (ref "U$8") (pin "2") (pinfunction "2_2") (pintype "passive"))
    )
    (net (code "45") (name "Net-(IC2-AO2')") (class "Default")
      (node (ref "IC2") (pin "5") (pinfunction "AO2_5") (pintype "output"))
      (node (ref "IC2") (pin "6") (pinfunction "AO2'_6") (pintype "output"))
      (node (ref "U$8") (pin "1") (pinfunction "1_1") (pintype "passive"))
    )
    (net (code "46") (name "Net-(IC2-BO1')") (class "Default")
      (node (ref "IC2") (pin "11") (pinfunction "BO1_11") (pintype "output"))
      (node (ref "IC2") (pin "12") (pinfunction "BO1'_12") (pintype "output"))
      (node (ref "U$7") (pin "1") (pinfunction "1_1") (pintype "passive"))
    )
    (net (code "47") (name "Net-(IC2-BO2')") (class "Default")
      (node (ref "IC2") (pin "7") (pinfunction "BO2_7") (pintype "output"))
      (node (ref "IC2") (pin "8") (pinfunction "BO2'_8") (pintype "output"))
      (node (ref "U$7") (pin "2") (pinfunction "2_2") (pintype "passive"))
    )
    (net (code "48") (name "Net-(JP1-Pad1)") (class "Default")
      (node (ref "JP1") (pin "1") (pinfunction "1_1") (pintype "passive"))
      (node (ref "JP2") (pin "2") (pinfunction "2_2") (pintype "passive"))
    )
    (net (code "49") (name "Net-(JP1-Pad2)") (class "Default")
      (node (ref "JP1") (pin "2") (pinfunction "2_2") (pintype "passive"))
      (node (ref "ON") (pin "3") (pinfunction "3_3") (pintype "bidirectional"))
      (node (ref "ON") (pin "6") (pinfunction "6_6") (pintype "bidirectional"))
    )
    (net (code "50") (name "Net-(LED1-PadA)") (class "Default")
      (node (ref "LED1") (pin "A") (pinfunction "A_A") (pintype "passive"))
      (node (ref "R26") (pin "1") (pinfunction "1_1") (pintype "passive"))
    )
    (net (code "51") (name "Net-(LED2-PadA)") (class "Default")
      (node (ref "LED2") (pin "A") (pinfunction "A_A") (pintype "passive"))
      (node (ref "R27") (pin "1") (pinfunction "1_1") (pintype "passive"))
    )
    (net (code "52") (name "Net-(LED3-PadA)") (class "Default")
      (node (ref "LED3") (pin "A") (pinfunction "A_A") (pintype "passive"))
      (node (ref "R28") (pin "1") (pinfunction "1_1") (pintype "passive"))
    )
    (net (code "53") (name "Net-(LED4-PadA)") (class "Default")
      (node (ref "LED4") (pin "A") (pinfunction "A_A") (pintype "passive"))
      (node (ref "R29") (pin "1") (pinfunction "1_1") (pintype "passive"))
    )
    (net (code "54") (name "Net-(M2A-C)") (class "Default")
      (node (ref "M2") (pin "-") (pinfunction "C_-") (pintype "passive"))
      (node (ref "R5") (pin "2") (pinfunction "2_2") (pintype "passive"))
    )
    (net (code "55") (name "Net-(M3A-C)") (class "Default")
      (node (ref "M3") (pin "-") (pinfunction "C_-") (pintype "passive"))
      (node (ref "R14") (pin "2") (pinfunction "2_2") (pintype "passive"))
    )
    (net (code "56") (name "Net-(M4A-C)") (class "Default")
      (node (ref "M4") (pin "-") (pinfunction "C_-") (pintype "passive"))
      (node (ref "R9") (pin "2") (pinfunction "2_2") (pintype "passive"))
    )
    (net (code "57") (name "Net-(M5A-C)") (class "Default")
      (node (ref "M5") (pin "-") (pinfunction "C_-") (pintype "passive"))
      (node (ref "R12") (pin "2") (pinfunction "2_2") (pintype "passive"))
    )
    (net (code "58") (name "Net-(M6A-C)") (class "Default")
      (node (ref "M6") (pin "-") (pinfunction "C_-") (pintype "passive"))
      (node (ref "R16") (pin "2") (pinfunction "2_2") (pintype "passive"))
    )
    (net (code "59") (name "Net-(M7A-C)") (class "Default")
      (node (ref "M7") (pin "-") (pinfunction "C_-") (pintype "passive"))
      (node (ref "R7") (pin "2") (pinfunction "2_2") (pintype "passive"))
    )
    (net (code "60") (name "Net-(Q7-D)") (class "Default")
      (node (ref "ON") (pin "2") (pinfunction "2_2") (pintype "bidirectional"))
      (node (ref "ON") (pin "5") (pinfunction "5_5") (pintype "bidirectional"))
      (node (ref "Q7") (pin "3") (pinfunction "D_3") (pintype "passive"))
    )
    (net (code "61") (name "Net-(Q9-D)") (class "Default")
      (node (ref "Q9") (pin "3") (pinfunction "D_3") (pintype "passive"))
      (node (ref "R22") (pin "2") (pinfunction "2_2") (pintype "passive"))
    )
    (net (code "62") (name "Net-(R6-Pad2)") (class "Default")
      (node (ref "R6") (pin "2") (pinfunction "2_2") (pintype "passive"))
      (node (ref "S4") (pin "1") (pinfunction "1_1") (pintype "passive"))
    )
    (net (code "63") (name "Net-(T2-D)") (class "Default")
      (node (ref "R16") (pin "1") (pinfunction "1_1") (pintype "passive"))
      (node (ref "T2") (pin "1") (pinfunction "D_1") (pintype "passive"))
    )
    (net (code "64") (name "Net-(T3-D)") (class "Default")
      (node (ref "R14") (pin "1") (pinfunction "1_1") (pintype "passive"))
      (node (ref "T3") (pin "1") (pinfunction "D_1") (pintype "passive"))
    )
    (net (code "65") (name "Net-(T4-D)") (class "Default")
      (node (ref "R9") (pin "1") (pinfunction "1_1") (pintype "passive"))
      (node (ref "T4") (pin "1") (pinfunction "D_1") (pintype "passive"))
    )
    (net (code "66") (name "Net-(T5-D)") (class "Default")
      (node (ref "R12") (pin "1") (pinfunction "1_1") (pintype "passive"))
      (node (ref "T5") (pin "1") (pinfunction "D_1") (pintype "passive"))
    )
    (net (code "67") (name "Net-(T6-D)") (class "Default")
      (node (ref "R5") (pin "1") (pinfunction "1_1") (pintype "passive"))
      (node (ref "T6") (pin "1") (pinfunction "D_1") (pintype "passive"))
    )
    (net (code "68") (name "Net-(T7-D)") (class "Default")
      (node (ref "R7") (pin "1") (pinfunction "1_1") (pintype "passive"))
      (node (ref "T7") (pin "1") (pinfunction "D_1") (pintype "passive"))
    )
    (net (code "69") (name "Net-(U1-EN)") (class "Default")
      (node (ref "R3_1") (pin "1") (pinfunction "1_1") (pintype "passive"))
      (node (ref "U1") (pin "4") (pinfunction "EN_4") (pintype "bidirectional"))
    )
    (net (code "70") (name "Net-(U1-FB)") (class "Default")
      (node (ref "R1_1") (pin "1") (pinfunction "1_1") (pintype "passive"))
      (node (ref "R2_1") (pin "2") (pinfunction "2_2") (pintype "passive"))
      (node (ref "U1") (pin "5") (pinfunction "FB_5") (pintype "bidirectional"))
    )
    (net (code "71") (name "Net-(U1-SW)") (class "Default")
      (node (ref "L1_1") (pin "1") (pinfunction "1_1") (pintype "passive"))
      (node (ref "U1") (pin "1") (pinfunction "SW_1") (pintype "bidirectional"))
    )
    (net (code "72") (name "Net-(U2-EN)") (class "Default")
      (node (ref "R3_2") (pin "1") (pinfunction "1_1") (pintype "passive"))
      (node (ref "U2") (pin "4") (pinfunction "EN_4") (pintype "bidirectional"))
    )
    (net (code "73") (name "Net-(U2-FB)") (class "Default")
      (node (ref "R1_2") (pin "1") (pinfunction "1_1") (pintype "passive"))
      (node (ref "R2_2") (pin "2") (pinfunction "2_2") (pintype "passive"))
      (node (ref "U2") (pin "5") (pinfunction "FB_5") (pintype "bidirectional"))
    )
    (net (code "74") (name "Net-(U2-SW)") (class "Default")
      (node (ref "L1_2") (pin "1") (pinfunction "1_1") (pintype "passive"))
      (node (ref "U2") (pin "1") (pinfunction "SW_1") (pintype "bidirectional"))
    )
    (net (code "75") (name "RST") (class "Default")
      (node (ref "C2") (pin "1") (pinfunction "1_1") (pintype "passive"))
      (node (ref "S3") (pin "4") (pinfunction "4_4") (pintype "passive"))
      (node (ref "U3") (pin "NRST") (pinfunction "NRST_NRST") (pintype "bidirectional"))
    )
    (net (code "76") (name "SPI2_CS1") (class "Default")
      (node (ref "U$9") (pin "1") (pinfunction "CS_1") (pintype "bidirectional"))
      (node (ref "U$9") (pin "1_1") (pinfunction "CS_1_1") (pintype "bidirectional"))
      (node (ref "U$9") (pin "1_2") (pinfunction "CS_1_2") (pintype "bidirectional"))
      (node (ref "U3") (pin "PB12") (pinfunction "PB12_PB12") (pintype "bidirectional"))
    )
    (net (code "77") (name "SPI2_CS2") (class "Default")
      (node (ref "U$10") (pin "1") (pinfunction "CS_1") (pintype "bidirectional"))
      (node (ref "U$10") (pin "1_1") (pinfunction "CS_1_1") (pintype "bidirectional"))
      (node (ref "U$10") (pin "1_2") (pinfunction "CS_1_2") (pintype "bidirectional"))
      (node (ref "U3") (pin "PB4") (pinfunction "PB4_PB4") (pintype "bidirectional"))
    )
    (net (code "78") (name "SPI2_MISO") (class "Default")
      (node (ref "U$10") (pin "3") (pinfunction "MISO_3") (pintype "bidirectional"))
      (node (ref "U$10") (pin "3_1") (pinfunction "MISO_3_1") (pintype "bidirectional"))
      (node (ref "U$10") (pin "3_2") (pinfunction "MISO_3_2") (pintype "bidirectional"))
      (node (ref "U$9") (pin "3") (pinfunction "MISO_3") (pintype "bidirectional"))
      (node (ref "U$9") (pin "3_1") (pinfunction "MISO_3_1") (pintype "bidirectional"))
      (node (ref "U$9") (pin "3_2") (pinfunction "MISO_3_2") (pintype "bidirectional"))
      (node (ref "U3") (pin "PB14") (pinfunction "PB14_PB14") (pintype "bidirectional"))
    )
    (net (code "79") (name "SPI2_MOSI") (class "Default")
      (node (ref "U$10") (pin "4") (pinfunction "MOSI_4") (pintype "bidirectional"))
      (node (ref "U$10") (pin "4_1") (pinfunction "MOSI_4_1") (pintype "bidirectional"))
      (node (ref "U$10") (pin "4_2") (pinfunction "MOSI_4_2") (pintype "bidirectional"))
      (node (ref "U$9") (pin "4") (pinfunction "MOSI_4") (pintype "bidirectional"))
      (node (ref "U$9") (pin "4_1") (pinfunction "MOSI_4_1") (pintype "bidirectional"))
      (node (ref "U$9") (pin "4_2") (pinfunction "MOSI_4_2") (pintype "bidirectional"))
      (node (ref "U3") (pin "PB15") (pinfunction "PB15_PB15") (pintype "bidirectional"))
    )
    (net (code "80") (name "SPI2_SCK") (class "Default")
      (node (ref "U$10") (pin "2") (pinfunction "CLK_2") (pintype "bidirectional"))
      (node (ref "U$10") (pin "2_1") (pinfunction "CLK_2_1") (pintype "bidirectional"))
      (node (ref "U$10") (pin "2_2") (pinfunction "CLK_2_2") (pintype "bidirectional"))
      (node (ref "U$9") (pin "2") (pinfunction "CLK_2") (pintype "bidirectional"))
      (node (ref "U$9") (pin "2_1") (pinfunction "CLK_2_1") (pintype "bidirectional"))
      (node (ref "U$9") (pin "2_2") (pinfunction "CLK_2_2") (pintype "bidirectional"))
      (node (ref "U3") (pin "PB13") (pinfunction "PB13_PB13") (pintype "bidirectional"))
    )
    (net (code "81") (name "SWCLK") (class "Default")
      (node (ref "D1") (pin "3") (pinfunction "3_3") (pintype "bidirectional"))
      (node (ref "SV1") (pin "7") (pinfunction "7_7") (pintype "passive"))
      (node (ref "U3") (pin "PA14") (pinfunction "PA14_PA14") (pintype "bidirectional"))
    )
    (net (code "82") (name "SWDIO") (class "Default")
      (node (ref "D1") (pin "4") (pinfunction "4_4") (pintype "bidirectional"))
      (node (ref "SV1") (pin "5") (pinfunction "5_5") (pintype "passive"))
      (node (ref "U3") (pin "PA13") (pinfunction "PA13_PA13") (pintype "bidirectional"))
    )
    (net (code "83") (name "USART3_RX") (class "Default")
      (node (ref "D1") (pin "6") (pinfunction "6_6") (pintype "bidirectional"))
      (node (ref "SV1") (pin "6") (pinfunction "6_6") (pintype "passive"))
      (node (ref "U3") (pin "PB11") (pinfunction "PB11_PB11") (pintype "bidirectional"))
    )
    (net (code "84") (name "USART3_TX") (class "Default")
      (node (ref "D1") (pin "1") (pinfunction "1_1") (pintype "bidirectional"))
      (node (ref "SV1") (pin "8") (pinfunction "8_8") (pintype "passive"))
      (node (ref "U3") (pin "PB10") (pinfunction "PB10_PB10") (pintype "bidirectional"))
    )
    (net (code "85") (name "VCAP_1") (class "Default")
      (node (ref "U3") (pin "VCAP_1") (pinfunction "VCAP_1_VCAP_1") (pintype "bidirectional"))
      (node (ref "VCAP_1") (pin "1") (pinfunction "1_1") (pintype "passive"))
    )
    (net (code "86") (name "VCAP_2") (class "Default")
      (node (ref "U3") (pin "VCAP_2") (pinfunction "VCAP_2_VCAP_2") (pintype "bidirectional"))
      (node (ref "VCAP_2") (pin "1") (pinfunction "1_1") (pintype "passive"))
    )
    (net (code "87") (name "unconnected-(IC1-AUX_CL-Pad7)") (class "Default")
      (node (ref "IC1") (pin "7") (pinfunction "AUX_CL_7") (pintype "bidirectional"))
    )
    (net (code "88") (name "unconnected-(IC1-AUX_DA-Pad6)") (class "Default")
      (node (ref "IC1") (pin "6") (pinfunction "AUX_DA_6") (pintype "bidirectional"))
    )
    (net (code "89") (name "unconnected-(ON-Pad1)") (class "Default")
      (node (ref "ON") (pin "1") (pinfunction "1_1") (pintype "bidirectional"))
    )
    (net (code "90") (name "unconnected-(ON-Pad4)") (class "Default")
      (node (ref "ON") (pin "4") (pinfunction "4_4") (pintype "bidirectional"))
    )
    (net (code "91") (name "unconnected-(S1-2-Pad3)") (class "Default")
      (node (ref "S1") (pin "3") (pinfunction "2_3") (pintype "passive"))
    )
    (net (code "92") (name "unconnected-(S1-3-Pad2)") (class "Default")
      (node (ref "S1") (pin "2") (pinfunction "3_2") (pintype "passive"))
    )
    (net (code "93") (name "unconnected-(S3-2-Pad3)") (class "Default")
      (node (ref "S3") (pin "3") (pinfunction "2_3") (pintype "passive"))
    )
    (net (code "94") (name "unconnected-(S3-3-Pad2)") (class "Default")
      (node (ref "S3") (pin "2") (pinfunction "3_2") (pintype "passive"))
    )
    (net (code "95") (name "unconnected-(S4-2-Pad3)") (class "Default")
      (node (ref "S4") (pin "3") (pinfunction "2_3") (pintype "passive"))
    )
    (net (code "96") (name "unconnected-(S4-3-Pad2)") (class "Default")
      (node (ref "S4") (pin "2") (pinfunction "3_2") (pintype "passive"))
    )
    (net (code "97") (name "unconnected-(U3-PadPA10)") (class "Default")
      (node (ref "U3") (pin "PA10") (pinfunction "PA10_PA10") (pintype "bidirectional"))
    )
    (net (code "98") (name "unconnected-(U3-PadPA11)") (class "Default")
      (node (ref "U3") (pin "PA11") (pinfunction "PA11_PA11") (pintype "bidirectional"))
    )
    (net (code "99") (name "unconnected-(U3-PadPA12)") (class "Default")
      (node (ref "U3") (pin "PA12") (pinfunction "PA12_PA12") (pintype "bidirectional"))
    )
    (net (code "100") (name "unconnected-(U3-PadPB0)") (class "Default")
      (node (ref "U3") (pin "PB0") (pinfunction "PB0_PB0") (pintype "bidirectional"))
    )
    (net (code "101") (name "unconnected-(U3-PadPB5)") (class "Default")
      (node (ref "U3") (pin "PB5") (pinfunction "PB5_PB5") (pintype "bidirectional"))
    )
    (net (code "102") (name "unconnected-(U3-PadPB6)") (class "Default")
      (node (ref "U3") (pin "PB6") (pinfunction "PB6_PB6") (pintype "bidirectional"))
    )
    (net (code "103") (name "unconnected-(U3-PadPC10)") (class "Default")
      (node (ref "U3") (pin "PC10") (pinfunction "PC10_PC10") (pintype "bidirectional"))
    )
    (net (code "104") (name "unconnected-(U3-PadPD2)") (class "Default")
      (node (ref "U3") (pin "PD2") (pinfunction "PD2_PD2") (pintype "bidirectional"))
    )
    (net (code "105") (name "unconnected-(U3-PadPH1)") (class "Default")
      (node (ref "U3") (pin "PH1") (pinfunction "PH1_PH1") (pintype "bidirectional"))
    )
  )
)
